# teensy_protocol_xl8r_3_6.net
KiCad netlist of a schematic drawn in EAGLE
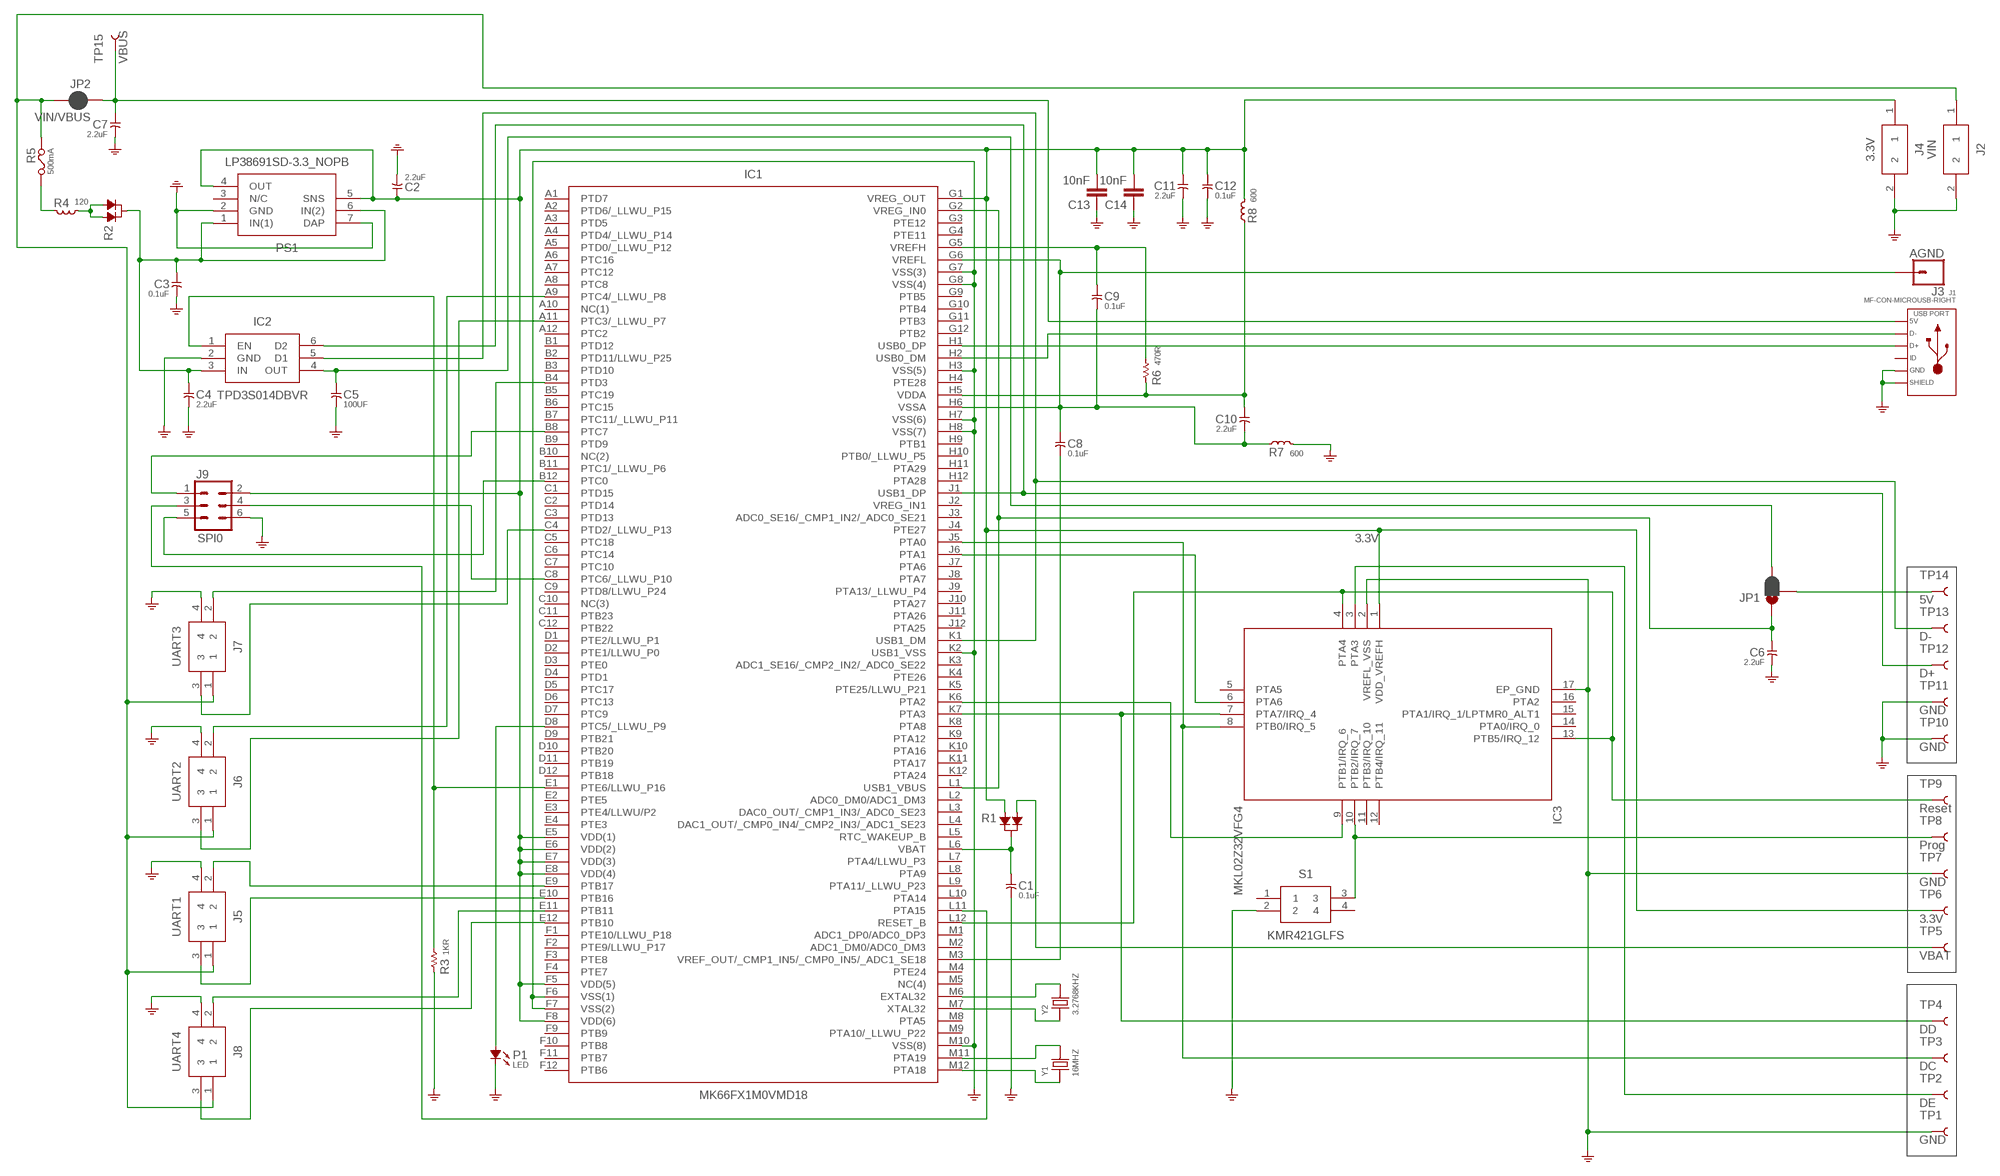
[diagram p0: schematic, sheet 1]

(export (version "E")
  (design (tool "Eeschema 10.0.6"))
  (components
    (comp (ref "C1")
      (value "0.1uF")
      (footprint "eagle-import:C0603")
      (fields (field (name "MF") "Murata Electronics") (field (name "MPN") "GRM188R71C104KA01D"))
      (libsource (lib "eagle-import") (part "CAPACITOR-0.1UF"))
    )
    (comp (ref "C2")
      (value "2.2uF")
      (footprint "eagle-import:C0805")
      (fields (field (name "MF") "Taiyo Yuden") (field (name "MPN") "TMK212B7225KG-TR"))
      (libsource (lib "eagle-import") (part "CAPACITOR-2.2UF"))
    )
    (comp (ref "C3")
      (value "0.1uF")
      (footprint "eagle-import:C0603")
      (fields (field (name "MF") "Murata Electronics") (field (name "MPN") "GRM188R71C104KA01D"))
      (libsource (lib "eagle-import") (part "CAPACITOR-0.1UF"))
    )
    (comp (ref "C4")
      (value "2.2uF")
      (footprint "eagle-import:C0805")
      (fields (field (name "MF") "Taiyo Yuden") (field (name "MPN") "TMK212B7225KG-TR"))
      (libsource (lib "eagle-import") (part "CAPACITOR-2.2UF"))
    )
    (comp (ref "C5")
      (value "100UF")
      (footprint "eagle-import:C1206")
      (libsource (lib "eagle-import") (part "CAPACITOR-100UF"))
    )
    (comp (ref "C6")
      (value "2.2uF")
      (footprint "eagle-import:C0805")
      (fields (field (name "MF") "Taiyo Yuden") (field (name "MPN") "TMK212B7225KG-TR"))
      (libsource (lib "eagle-import") (part "CAPACITOR-2.2UF"))
    )
    (comp (ref "C7")
      (value "2.2uF")
      (footprint "eagle-import:C0805")
      (fields (field (name "MF") "Taiyo Yuden") (field (name "MPN") "TMK212B7225KG-TR"))
      (libsource (lib "eagle-import") (part "CAPACITOR-2.2UF"))
    )
    (comp (ref "C8")
      (value "0.1uF")
      (footprint "eagle-import:C0603")
      (fields (field (name "MF") "Murata Electronics") (field (name "MPN") "GRM188R71C104KA01D"))
      (libsource (lib "eagle-import") (part "CAPACITOR-0.1UF"))
    )
    (comp (ref "C9")
      (value "0.1uF")
      (footprint "eagle-import:C0603")
      (fields (field (name "MF") "Murata Electronics") (field (name "MPN") "GRM188R71C104KA01D"))
      (libsource (lib "eagle-import") (part "CAPACITOR-0.1UF"))
    )
    (comp (ref "C10")
      (value "2.2uF")
      (footprint "eagle-import:C0805")
      (fields (field (name "MF") "Taiyo Yuden") (field (name "MPN") "TMK212B7225KG-TR"))
      (libsource (lib "eagle-import") (part "CAPACITOR-2.2UF"))
    )
    (comp (ref "C11")
      (value "2.2uF")
      (footprint "eagle-import:C0805")
      (fields (field (name "MF") "Taiyo Yuden") (field (name "MPN") "TMK212B7225KG-TR"))
      (libsource (lib "eagle-import") (part "CAPACITOR-2.2UF"))
    )
    (comp (ref "C12")
      (value "0.1uF")
      (footprint "eagle-import:C0603")
      (fields (field (name "MF") "Murata Electronics") (field (name "MPN") "GRM188R71C104KA01D"))
      (libsource (lib "eagle-import") (part "CAPACITOR-0.1UF"))
    )
    (comp (ref "C13")
      (value "10nF")
      (footprint "eagle-import:0603")
      (libsource (lib "eagle-import") (part "10NF-0603-50V-10%"))
    )
    (comp (ref "C14")
      (value "10nF")
      (footprint "eagle-import:0603")
      (libsource (lib "eagle-import") (part "10NF-0603-50V-10%"))
    )
    (comp (ref "IC1")
      (value "MK66FX1M0VMD18")
      (footprint "eagle-import:BGA144C100P12X12_1300X1300X170")
      (libsource (lib "eagle-import") (part "MK66FX1M0VMD18"))
    )
    (comp (ref "IC2")
      (value "TPD3S014DBVR")
      (footprint "eagle-import:SOT95P280X145-6N")
      (fields (field (name "RS_PART_NUMBER") "9009703P"))
      (libsource (lib "eagle-import") (part "TPD3S014DBVR"))
    )
    (comp (ref "IC3")
      (value "MKL02Z32VFG4")
      (footprint "eagle-import:QFN50P300X300X65-17N")
      (fields (field (name "RS_PART_NUMBER") "7884723"))
      (libsource (lib "eagle-import") (part "MKL02Z32VFG4"))
    )
    (comp (ref "J1")
      (value "MF-CON-MICROUSB-RIGHT")
      (footprint "eagle-import:MICROUSB-RIGHT")
      (fields (field (name "HOUSEPART") "YES"))
      (libsource (lib "eagle-import") (part "USB_MICRO_RIGHT"))
    )
    (comp (ref "J2")
      (value "VIN")
      (footprint "eagle-import:SM02B-GHS-TB")
      (fields
        (field (name "MANUFACTURER_PART_NUMBER") "SM02B-GHS-TB(LF)(SN)")
        (field (name "RS_PART_NUMBER") "7521790P")
      )
      (libsource (lib "eagle-import") (part "SM02B-GHS-TB(LF)(SN)"))
    )
    (comp (ref "J3")
      (value "AGND")
      (footprint "eagle-import:1X01")
      (libsource (lib "eagle-import") (part "CONN_01"))
    )
    (comp (ref "J4")
      (value "3.3V")
      (footprint "eagle-import:SM02B-GHS-TB")
      (fields
        (field (name "MANUFACTURER_PART_NUMBER") "SM02B-GHS-TB(LF)(SN)")
        (field (name "RS_PART_NUMBER") "7521790P")
      )
      (libsource (lib "eagle-import") (part "SM02B-GHS-TB(LF)(SN)"))
    )
    (comp (ref "J5")
      (value "UART1")
      (footprint "eagle-import:SM04B-GHS-TB")
      (fields
        (field (name "MANUFACTURER_PART_NUMBER") "SM04B-GHS-TB(LF)(SN)")
        (field (name "RS_PART_NUMBER") "7521797")
      )
      (libsource (lib "eagle-import") (part "SM04B-GHS-TB(LF)(SN)"))
    )
    (comp (ref "J6")
      (value "UART2")
      (footprint "eagle-import:SM04B-GHS-TB")
      (fields
        (field (name "MANUFACTURER_PART_NUMBER") "SM04B-GHS-TB(LF)(SN)")
        (field (name "RS_PART_NUMBER") "7521797")
      )
      (libsource (lib "eagle-import") (part "SM04B-GHS-TB(LF)(SN)"))
    )
    (comp (ref "J7")
      (value "UART3")
      (footprint "eagle-import:SM04B-GHS-TB")
      (fields
        (field (name "MANUFACTURER_PART_NUMBER") "SM04B-GHS-TB(LF)(SN)")
        (field (name "RS_PART_NUMBER") "7521797")
      )
      (libsource (lib "eagle-import") (part "SM04B-GHS-TB(LF)(SN)"))
    )
    (comp (ref "J8")
      (value "UART4")
      (footprint "eagle-import:SM04B-GHS-TB")
      (fields
        (field (name "MANUFACTURER_PART_NUMBER") "SM04B-GHS-TB(LF)(SN)")
        (field (name "RS_PART_NUMBER") "7521797")
      )
      (libsource (lib "eagle-import") (part "SM04B-GHS-TB(LF)(SN)"))
    )
    (comp (ref "J9")
      (value "SPI0")
      (footprint "eagle-import:2X3")
      (libsource (lib "eagle-import") (part "CONN_03X2FEMALE"))
    )
    (comp (ref "JP1")
      (value "JUMPER-SMT_3_1-NC_PASTE_SILK")
      (footprint "eagle-import:SMT-JUMPER_3_1-NC_PASTE_SILK")
      (libsource (lib "eagle-import") (part "JUMPER-SMT_3_1-NC_PASTE_SILK"))
    )
    (comp (ref "JP2")
      (value "VIN/VBUS")
      (footprint "eagle-import:SMT-JUMPER_2_NC_PASTE_SILK")
      (libsource (lib "eagle-import") (part "JUMPER-SMT_2_NC_PASTE_SILK"))
    )
    (comp (ref "P1")
      (value "LED")
      (footprint "eagle-import:LED-0805")
      (fields (field (name "MF") "ROHM Semiconductor") (field (name "MPN") "SML-211DTT86"))
      (libsource (lib "eagle-import") (part "LED"))
    )
    (comp (ref "PS1")
      (value "LP38691SD-3.3_NOPB")
      (footprint "eagle-import:SON95P300X300X80-7N")
      (fields
        (field (name "MANUFACTURER_PART_NUMBER") "LP38691SD-3.3/NOPB")
        (field (name "RS_PART_NUMBER") "7616605P")
      )
      (libsource (lib "eagle-import") (part "LP38691SD-3.3_NOPB"))
    )
    (comp (ref "R1")
      (value "DIODE_DUAL")
      (footprint "eagle-import:SOT-23")
      (fields (field (name "MF") "NXP Semiconductors") (field (name "MPN") "BAT54C,215"))
      (libsource (lib "eagle-import") (part "DIODE_DUAL"))
    )
    (comp (ref "R2")
      (value "DIODE_DUAL")
      (footprint "eagle-import:SOT-23")
      (fields (field (name "MF") "NXP Semiconductors") (field (name "MPN") "BAT54C,215"))
      (libsource (lib "eagle-import") (part "DIODE_DUAL"))
    )
    (comp (ref "R3")
      (value "1KR")
      (footprint "eagle-import:R0603")
      (fields (field (name "MF") "Vishay") (field (name "MPN") "CRCW06031K00FKEA"))
      (libsource (lib "eagle-import") (part "RESISTOR-1KR"))
    )
    (comp (ref "R4")
      (value "120")
      (footprint "eagle-import:L0603")
      (fields (field (name "MF") "Murata Electronics") (field (name "MPN") " BLM18AG601SN1D"))
      (libsource (lib "eagle-import") (part "FERRITE"))
    )
    (comp (ref "R5")
      (value "500mA")
      (footprint "eagle-import:F0805")
      (fields (field (name "MF") "Bel Fuse") (field (name "MPN") "0ZCK0050FF2E"))
      (libsource (lib "eagle-import") (part "FUSE"))
    )
    (comp (ref "R6")
      (value "470R")
      (footprint "eagle-import:R0603")
      (fields (field (name "MF") "Vishay") (field (name "MPN") "CRCW0603470RFKEA"))
      (libsource (lib "eagle-import") (part "RESISTOR-470R"))
    )
    (comp (ref "R7")
      (value "600")
      (footprint "eagle-import:L0603")
      (fields (field (name "MF") "Murata Electronics") (field (name "MPN") " BLM18AG601SN1D"))
      (libsource (lib "eagle-import") (part "FERRITE"))
    )
    (comp (ref "R8")
      (value "600")
      (footprint "eagle-import:L0603")
      (fields (field (name "MF") "Murata Electronics") (field (name "MPN") " BLM18AG601SN1D"))
      (libsource (lib "eagle-import") (part "FERRITE"))
    )
    (comp (ref "S1")
      (value "KMR421GLFS")
      (footprint "eagle-import:KMR_2")
      (libsource (lib "eagle-import") (part "KMR421GLFS"))
    )
    (comp (ref "TP1")
      (value "GND")
      (footprint "eagle-import:PAD.03X.03")
      (libsource (lib "eagle-import") (part "TEST-POINT3"))
    )
    (comp (ref "TP2")
      (value "DE")
      (footprint "eagle-import:PAD.03X.03")
      (libsource (lib "eagle-import") (part "TEST-POINT3"))
    )
    (comp (ref "TP3")
      (value "DC")
      (footprint "eagle-import:PAD.03X.03")
      (libsource (lib "eagle-import") (part "TEST-POINT3"))
    )
    (comp (ref "TP4")
      (value "DD")
      (footprint "eagle-import:PAD.03X.03")
      (libsource (lib "eagle-import") (part "TEST-POINT3"))
    )
    (comp (ref "TP5")
      (value "VBAT")
      (footprint "eagle-import:PAD.03X.03")
      (libsource (lib "eagle-import") (part "TEST-POINT3"))
    )
    (comp (ref "TP6")
      (value "3.3V")
      (footprint "eagle-import:PAD.03X.03")
      (libsource (lib "eagle-import") (part "TEST-POINT3"))
    )
    (comp (ref "TP7")
      (value "GND")
      (footprint "eagle-import:PAD.03X.03")
      (libsource (lib "eagle-import") (part "TEST-POINT3"))
    )
    (comp (ref "TP8")
      (value "Prog")
      (footprint "eagle-import:PAD.03X.03")
      (libsource (lib "eagle-import") (part "TEST-POINT3"))
    )
    (comp (ref "TP9")
      (value "Reset")
      (footprint "eagle-import:PAD.03X.03")
      (libsource (lib "eagle-import") (part "TEST-POINT3"))
    )
    (comp (ref "TP10")
      (value "GND")
      (footprint "eagle-import:PAD.03X.03")
      (libsource (lib "eagle-import") (part "TEST-POINT3"))
    )
    (comp (ref "TP11")
      (value "GND")
      (footprint "eagle-import:PAD.03X.03")
      (libsource (lib "eagle-import") (part "TEST-POINT3"))
    )
    (comp (ref "TP12")
      (value "D+")
      (footprint "eagle-import:PAD.03X.03")
      (libsource (lib "eagle-import") (part "TEST-POINT3"))
    )
    (comp (ref "TP13")
      (value "D-")
      (footprint "eagle-import:PAD.03X.03")
      (libsource (lib "eagle-import") (part "TEST-POINT3"))
    )
    (comp (ref "TP14")
      (value "5V")
      (footprint "eagle-import:PAD.03X.03")
      (libsource (lib "eagle-import") (part "TEST-POINT3"))
    )
    (comp (ref "TP15")
      (value "VBUS")
      (footprint "eagle-import:PAD.03X.03")
      (libsource (lib "eagle-import") (part "TEST-POINT3"))
    )
    (comp (ref "Y1")
      (value "16MHZ")
      (footprint "eagle-import:X2-SMD-5.0X3.2X1.3MM")
      (fields (field (name "MPN") "X053201602002"))
      (libsource (lib "eagle-import") (part "SMD-CRYSTAL-16MHZ-8PF-20PPM-40R(2P-5.0X3.2MM)"))
    )
    (comp (ref "Y2")
      (value "3.2768KHZ")
      (footprint "eagle-import:X2-SMD-L2.0X1.2X0.55MM")
      (fields (field (name "MPN") "FC-12M"))
      (libsource (lib "eagle-import") (part "SMD-CRYSTAL-32.768KHZ-12.5PF-20PPM-90K(2P-L2.0X1.2MM)"))
    )
  )
  (nets
    (net (code "1") (name "/3.3V") (class "Default")
      (node (ref "C11") (pin "1") (pinfunction "1_1") (pintype "passive"))
      (node (ref "C12") (pin "1") (pinfunction "1_1") (pintype "passive"))
      (node (ref "C13") (pin "2") (pinfunction "2_2") (pintype "passive"))
      (node (ref "C14") (pin "2") (pinfunction "2_2") (pintype "passive"))
      (node (ref "C2") (pin "1") (pinfunction "1_1") (pintype "passive"))
      (node (ref "IC1") (pin "E5") (pinfunction "VDD(1)_E5") (pintype "passive"))
      (node (ref "IC1") (pin "E6") (pinfunction "VDD(2)_E6") (pintype "passive"))
      (node (ref "IC1") (pin "E7") (pinfunction "VDD(3)_E7") (pintype "passive"))
      (node (ref "IC1") (pin "E8") (pinfunction "VDD(4)_E8") (pintype "passive"))
      (node (ref "IC1") (pin "F5") (pinfunction "VDD(5)_F5") (pintype "passive"))
      (node (ref "IC1") (pin "F8") (pinfunction "VDD(6)_F8") (pintype "passive"))
      (node (ref "IC1") (pin "G1") (pinfunction "VREG_OUT_G1") (pintype "passive"))
      (node (ref "IC3") (pin "1") (pinfunction "VDD_VREFH_1") (pintype "power_in"))
      (node (ref "J4") (pin "1") (pinfunction "1_1") (pintype "passive"))
      (node (ref "J9") (pin "2") (pinfunction "2_2") (pintype "bidirectional"))
      (node (ref "PS1") (pin "4") (pinfunction "OUT_4") (pintype "output"))
      (node (ref "PS1") (pin "5") (pinfunction "SNS_5") (pintype "output"))
      (node (ref "R1") (pin "2") (pinfunction "2_2") (pintype "bidirectional"))
      (node (ref "R8") (pin "2") (pinfunction "2_2") (pintype "passive"))
      (node (ref "TP6") (pin "P$1") (pinfunction "1_P$1") (pintype "bidirectional"))
    )
    (net (code "2") (name "GND") (class "Default")
      (node (ref "C1") (pin "2") (pinfunction "2_2") (pintype "passive"))
      (node (ref "C11") (pin "2") (pinfunction "2_2") (pintype "passive"))
      (node (ref "C12") (pin "2") (pinfunction "2_2") (pintype "passive"))
      (node (ref "C13") (pin "1") (pinfunction "1_1") (pintype "passive"))
      (node (ref "C14") (pin "1") (pinfunction "1_1") (pintype "passive"))
      (node (ref "C2") (pin "2") (pinfunction "2_2") (pintype "passive"))
      (node (ref "C3") (pin "2") (pinfunction "2_2") (pintype "passive"))
      (node (ref "C4") (pin "2") (pinfunction "2_2") (pintype "passive"))
      (node (ref "C5") (pin "2") (pinfunction "2_2") (pintype "passive"))
      (node (ref "C6") (pin "2") (pinfunction "2_2") (pintype "passive"))
      (node (ref "C7") (pin "2") (pinfunction "2_2") (pintype "passive"))
      (node (ref "IC1") (pin "F6") (pinfunction "VSS(1)_F6") (pintype "passive"))
      (node (ref "IC1") (pin "F7") (pinfunction "VSS(2)_F7") (pintype "passive"))
      (node (ref "IC1") (pin "G7") (pinfunction "VSS(3)_G7") (pintype "passive"))
      (node (ref "IC1") (pin "G8") (pinfunction "VSS(4)_G8") (pintype "passive"))
      (node (ref "IC1") (pin "H3") (pinfunction "VSS(5)_H3") (pintype "passive"))
      (node (ref "IC1") (pin "H7") (pinfunction "VSS(6)_H7") (pintype "passive"))
      (node (ref "IC1") (pin "H8") (pinfunction "VSS(7)_H8") (pintype "passive"))
      (node (ref "IC1") (pin "K2") (pinfunction "USB1_VSS_K2") (pintype "passive"))
      (node (ref "IC1") (pin "M10") (pinfunction "VSS(8)_M10") (pintype "passive"))
      (node (ref "IC2") (pin "2") (pinfunction "GND_2") (pintype "power_in"))
      (node (ref "IC3") (pin "17") (pinfunction "EP_GND_17") (pintype "power_in"))
      (node (ref "IC3") (pin "2") (pinfunction "VREFL_VSS_2") (pintype "power_in"))
      (node (ref "J1") (pin "5") (pinfunction "GND_5") (pintype "power_in"))
      (node (ref "J1") (pin "S1") (pinfunction "SLD_S1") (pintype "power_in"))
      (node (ref "J1") (pin "S2") (pinfunction "SLD_S2") (pintype "power_in"))
      (node (ref "J1") (pin "S3") (pinfunction "SLD_S3") (pintype "power_in"))
      (node (ref "J1") (pin "S4") (pinfunction "SLD_S4") (pintype "power_in"))
      (node (ref "J1") (pin "S5") (pinfunction "SLD_S5") (pintype "power_in"))
      (node (ref "J1") (pin "S6") (pinfunction "SLD_S6") (pintype "power_in"))
      (node (ref "J2") (pin "2") (pinfunction "2_2") (pintype "passive"))
      (node (ref "J4") (pin "2") (pinfunction "2_2") (pintype "passive"))
      (node (ref "J5") (pin "4") (pinfunction "4_4") (pintype "passive"))
      (node (ref "J6") (pin "4") (pinfunction "4_4") (pintype "passive"))
      (node (ref "J7") (pin "4") (pinfunction "4_4") (pintype "passive"))
      (node (ref "J8") (pin "4") (pinfunction "4_4") (pintype "passive"))
      (node (ref "J9") (pin "6") (pinfunction "6_6") (pintype "bidirectional"))
      (node (ref "P1") (pin "-") (pinfunction "-_-") (pintype "passive"))
      (node (ref "PS1") (pin "2") (pinfunction "GND_2") (pintype "power_in"))
      (node (ref "PS1") (pin "7") (pinfunction "DAP_7") (pintype "passive"))
      (node (ref "R3") (pin "1") (pinfunction "1_1") (pintype "passive"))
      (node (ref "R7") (pin "2") (pinfunction "2_2") (pintype "passive"))
      (node (ref "S1") (pin "2") (pinfunction "2_2") (pintype "passive"))
      (node (ref "TP1") (pin "P$1") (pinfunction "1_P$1") (pintype "bidirectional"))
      (node (ref "TP10") (pin "P$1") (pinfunction "1_P$1") (pintype "bidirectional"))
      (node (ref "TP11") (pin "P$1") (pinfunction "1_P$1") (pintype "bidirectional"))
      (node (ref "TP7") (pin "P$1") (pinfunction "1_P$1") (pintype "bidirectional"))
    )
    (net (code "3") (name "Net-(IC1-EXTAL32)") (class "Default")
      (node (ref "IC1") (pin "M6") (pinfunction "EXTAL32_M6") (pintype "passive"))
      (node (ref "Y2") (pin "2") (pinfunction "2_2") (pintype "passive"))
    )
    (net (code "4") (name "Net-(IC1-PTA0)") (class "Default")
      (node (ref "IC1") (pin "J5") (pinfunction "PTA0_J5") (pintype "passive"))
      (node (ref "IC3") (pin "8") (pinfunction "PTB0/IRQ_5_8") (pintype "passive"))
      (node (ref "TP3") (pin "P$1") (pinfunction "1_P$1") (pintype "bidirectional"))
    )
    (net (code "5") (name "Net-(IC1-PTA1)") (class "Default")
      (node (ref "IC1") (pin "J6") (pinfunction "PTA1_J6") (pintype "passive"))
      (node (ref "IC3") (pin "6") (pinfunction "PTA6_6") (pintype "passive"))
    )
    (net (code "6") (name "Net-(IC1-PTA2)") (class "Default")
      (node (ref "IC1") (pin "K6") (pinfunction "PTA2_K6") (pintype "passive"))
      (node (ref "IC3") (pin "9") (pinfunction "PTB1/IRQ_6_9") (pintype "passive"))
    )
    (net (code "7") (name "Net-(IC1-PTA3)") (class "Default")
      (node (ref "IC1") (pin "K7") (pinfunction "PTA3_K7") (pintype "passive"))
      (node (ref "IC3") (pin "7") (pinfunction "PTA7/IRQ_4_7") (pintype "passive"))
      (node (ref "TP4") (pin "P$1") (pinfunction "1_P$1") (pintype "bidirectional"))
    )
    (net (code "8") (name "Net-(IC1-PTA15)") (class "Default")
      (node (ref "IC1") (pin "L11") (pinfunction "PTA15_L11") (pintype "passive"))
      (node (ref "J9") (pin "3") (pinfunction "3_3") (pintype "bidirectional"))
    )
    (net (code "9") (name "Net-(IC1-PTA18)") (class "Default")
      (node (ref "IC1") (pin "M12") (pinfunction "PTA18_M12") (pintype "passive"))
      (node (ref "Y1") (pin "1") (pinfunction "1_1") (pintype "passive"))
    )
    (net (code "10") (name "Net-(IC1-PTA19)") (class "Default")
      (node (ref "IC1") (pin "M11") (pinfunction "PTA19_M11") (pintype "passive"))
      (node (ref "Y1") (pin "2") (pinfunction "2_2") (pintype "passive"))
    )
    (net (code "11") (name "Net-(IC1-PTB10)") (class "Default")
      (node (ref "IC1") (pin "E12") (pinfunction "PTB10_E12") (pintype "passive"))
      (node (ref "J8") (pin "3") (pinfunction "3_3") (pintype "passive"))
    )
    (net (code "12") (name "Net-(IC1-PTB11)") (class "Default")
      (node (ref "IC1") (pin "E11") (pinfunction "PTB11_E11") (pintype "passive"))
      (node (ref "J8") (pin "2") (pinfunction "2_2") (pintype "passive"))
    )
    (net (code "13") (name "Net-(IC1-PTB16)") (class "Default")
      (node (ref "IC1") (pin "E10") (pinfunction "PTB16_E10") (pintype "passive"))
      (node (ref "J5") (pin "3") (pinfunction "3_3") (pintype "passive"))
    )
    (net (code "14") (name "Net-(IC1-PTB17)") (class "Default")
      (node (ref "IC1") (pin "E9") (pinfunction "PTB17_E9") (pintype "passive"))
      (node (ref "J5") (pin "2") (pinfunction "2_2") (pintype "passive"))
    )
    (net (code "15") (name "Net-(IC1-PTC0)") (class "Default")
      (node (ref "IC1") (pin "B12") (pinfunction "PTC0_B12") (pintype "passive"))
      (node (ref "J9") (pin "5") (pinfunction "5_5") (pintype "bidirectional"))
    )
    (net (code "16") (name "Net-(IC1-PTC3{slash}_LLWU_P7)") (class "Default")
      (node (ref "IC1") (pin "A11") (pinfunction "PTC3/_LLWU_P7_A11") (pintype "passive"))
      (node (ref "J6") (pin "3") (pinfunction "3_3") (pintype "passive"))
    )
    (net (code "17") (name "Net-(IC1-PTC4{slash}_LLWU_P8)") (class "Default")
      (node (ref "IC1") (pin "A9") (pinfunction "PTC4/_LLWU_P8_A9") (pintype "passive"))
      (node (ref "J6") (pin "2") (pinfunction "2_2") (pintype "passive"))
    )
    (net (code "18") (name "Net-(IC1-PTC5{slash}_LLWU_P9)") (class "Default")
      (node (ref "IC1") (pin "D8") (pinfunction "PTC5/_LLWU_P9_D8") (pintype "passive"))
      (node (ref "P1") (pin "+") (pinfunction "+_+") (pintype "passive"))
    )
    (net (code "19") (name "Net-(IC1-PTC6{slash}_LLWU_P10)") (class "Default")
      (node (ref "IC1") (pin "C8") (pinfunction "PTC6/_LLWU_P10_C8") (pintype "passive"))
      (node (ref "J9") (pin "4") (pinfunction "4_4") (pintype "bidirectional"))
    )
    (net (code "20") (name "Net-(IC1-PTC7)") (class "Default")
      (node (ref "IC1") (pin "B8") (pinfunction "PTC7_B8") (pintype "passive"))
      (node (ref "J9") (pin "1") (pinfunction "1_1") (pintype "bidirectional"))
    )
    (net (code "21") (name "Net-(IC1-PTD2{slash}_LLWU_P13)") (class "Default")
      (node (ref "IC1") (pin "C4") (pinfunction "PTD2/_LLWU_P13_C4") (pintype "passive"))
      (node (ref "J7") (pin "3") (pinfunction "3_3") (pintype "passive"))
    )
    (net (code "22") (name "Net-(IC1-PTD3)") (class "Default")
      (node (ref "IC1") (pin "B4") (pinfunction "PTD3_B4") (pintype "passive"))
      (node (ref "J7") (pin "2") (pinfunction "2_2") (pintype "passive"))
    )
    (net (code "23") (name "Net-(IC1-PTE6{slash}LLWU_P16)") (class "Default")
      (node (ref "IC1") (pin "E1") (pinfunction "PTE6/LLWU_P16_E1") (pintype "passive"))
      (node (ref "IC2") (pin "1") (pinfunction "EN_1") (pintype "input"))
      (node (ref "R3") (pin "2") (pinfunction "2_2") (pintype "passive"))
    )
    (net (code "24") (name "Net-(IC1-RESET_B)") (class "Default")
      (node (ref "IC1") (pin "L12") (pinfunction "RESET_B_L12") (pintype "passive"))
      (node (ref "IC3") (pin "13") (pinfunction "PTB5/IRQ_12_13") (pintype "passive"))
      (node (ref "IC3") (pin "4") (pinfunction "PTA4_4") (pintype "passive"))
      (node (ref "TP9") (pin "P$1") (pinfunction "1_P$1") (pintype "bidirectional"))
    )
    (net (code "25") (name "Net-(IC1-USB0_DM)") (class "Default")
      (node (ref "IC1") (pin "H2") (pinfunction "USB0_DM_H2") (pintype "passive"))
      (node (ref "J1") (pin "2") (pinfunction "D-_2") (pintype "bidirectional"))
    )
    (net (code "26") (name "Net-(IC1-USB0_DP)") (class "Default")
      (node (ref "IC1") (pin "H1") (pinfunction "USB0_DP_H1") (pintype "passive"))
      (node (ref "J1") (pin "3") (pinfunction "D+_3") (pintype "bidirectional"))
    )
    (net (code "27") (name "Net-(IC1-USB1_DM)") (class "Default")
      (node (ref "IC1") (pin "K1") (pinfunction "USB1_DM_K1") (pintype "passive"))
      (node (ref "IC2") (pin "5") (pinfunction "D1_5") (pintype "bidirectional"))
      (node (ref "TP13") (pin "P$1") (pinfunction "1_P$1") (pintype "bidirectional"))
    )
    (net (code "28") (name "Net-(IC1-USB1_DP)") (class "Default")
      (node (ref "IC1") (pin "J1") (pinfunction "USB1_DP_J1") (pintype "passive"))
      (node (ref "IC2") (pin "6") (pinfunction "D2_6") (pintype "bidirectional"))
      (node (ref "TP12") (pin "P$1") (pinfunction "1_P$1") (pintype "bidirectional"))
    )
    (net (code "29") (name "Net-(IC1-USB1_VBUS)") (class "Default")
      (node (ref "C6") (pin "1") (pinfunction "1_1") (pintype "passive"))
      (node (ref "IC1") (pin "G2") (pinfunction "VREG_IN0_G2") (pintype "passive"))
      (node (ref "IC1") (pin "L1") (pinfunction "USB1_VBUS_L1") (pintype "passive"))
      (node (ref "JP1") (pin "1") (pinfunction "1_1") (pintype "passive"))
    )
    (net (code "30") (name "Net-(IC1-VBAT)") (class "Default")
      (node (ref "C1") (pin "1") (pinfunction "1_1") (pintype "passive"))
      (node (ref "IC1") (pin "L6") (pinfunction "VBAT_L6") (pintype "passive"))
      (node (ref "R1") (pin "3") (pinfunction "3_3") (pintype "bidirectional"))
    )
    (net (code "31") (name "Net-(IC1-VDDA)") (class "Default")
      (node (ref "C10") (pin "1") (pinfunction "1_1") (pintype "passive"))
      (node (ref "IC1") (pin "H5") (pinfunction "VDDA_H5") (pintype "passive"))
      (node (ref "R6") (pin "1") (pinfunction "1_1") (pintype "passive"))
      (node (ref "R8") (pin "1") (pinfunction "1_1") (pintype "passive"))
    )
    (net (code "32") (name "Net-(IC1-VREFH)") (class "Default")
      (node (ref "C9") (pin "1") (pinfunction "1_1") (pintype "passive"))
      (node (ref "IC1") (pin "G5") (pinfunction "VREFH_G5") (pintype "passive"))
      (node (ref "R6") (pin "2") (pinfunction "2_2") (pintype "passive"))
    )
    (net (code "33") (name "Net-(IC1-VREFL)") (class "Default")
      (node (ref "C10") (pin "2") (pinfunction "2_2") (pintype "passive"))
      (node (ref "C8") (pin "1") (pinfunction "1_1") (pintype "passive"))
      (node (ref "C9") (pin "2") (pinfunction "2_2") (pintype "passive"))
      (node (ref "IC1") (pin "G6") (pinfunction "VREFL_G6") (pintype "passive"))
      (node (ref "IC1") (pin "H6") (pinfunction "VSSA_H6") (pintype "passive"))
      (node (ref "J3") (pin "1") (pinfunction "1_1") (pintype "passive"))
      (node (ref "R7") (pin "1") (pinfunction "1_1") (pintype "passive"))
    )
    (net (code "34") (name "Net-(IC1-VREF_OUT{slash}_CMP1_IN5{slash}_CMP0_IN5{slash}_ADC1_SE18)") (class "Default")
      (node (ref "C8") (pin "2") (pinfunction "2_2") (pintype "passive"))
      (node (ref "IC1") (pin "M3") (pinfunction "VREF_OUT/_CMP1_IN5/_CMP0_IN5/_ADC1_SE18_M3") (pintype "passive"))
    )
    (net (code "35") (name "Net-(IC1-XTAL32)") (class "Default")
      (node (ref "IC1") (pin "M7") (pinfunction "XTAL32_M7") (pintype "passive"))
      (node (ref "Y2") (pin "1") (pinfunction "1_1") (pintype "passive"))
    )
    (net (code "36") (name "Net-(IC2-IN)") (class "Default")
      (node (ref "C3") (pin "1") (pinfunction "1_1") (pintype "passive"))
      (node (ref "C4") (pin "1") (pinfunction "1_1") (pintype "passive"))
      (node (ref "IC2") (pin "3") (pinfunction "IN_3") (pintype "input"))
      (node (ref "PS1") (pin "1") (pinfunction "IN(1)_1") (pintype "input"))
      (node (ref "PS1") (pin "6") (pinfunction "IN(2)_6") (pintype "input"))
      (node (ref "R2") (pin "3") (pinfunction "3_3") (pintype "bidirectional"))
    )
    (net (code "37") (name "Net-(IC2-OUT)") (class "Default")
      (node (ref "C5") (pin "1") (pinfunction "1_1") (pintype "passive"))
      (node (ref "IC2") (pin "4") (pinfunction "OUT_4") (pintype "output"))
      (node (ref "JP1") (pin "3") (pinfunction "3_3") (pintype "passive"))
    )
    (net (code "38") (name "Net-(IC3-PTA3)") (class "Default")
      (node (ref "IC3") (pin "3") (pinfunction "PTA3_3") (pintype "passive"))
      (node (ref "TP2") (pin "P$1") (pinfunction "1_P$1") (pintype "bidirectional"))
    )
    (net (code "39") (name "Net-(IC3-PTB2{slash}IRQ_7)") (class "Default")
      (node (ref "IC3") (pin "10") (pinfunction "PTB2/IRQ_7_10") (pintype "passive"))
      (node (ref "S1") (pin "3") (pinfunction "3_3") (pintype "passive"))
      (node (ref "TP8") (pin "P$1") (pinfunction "1_P$1") (pintype "bidirectional"))
    )
    (net (code "40") (name "Net-(J1-5V)") (class "Default")
      (node (ref "C7") (pin "1") (pinfunction "1_1") (pintype "passive"))
      (node (ref "J1") (pin "1") (pinfunction "5V_1") (pintype "power_in"))
      (node (ref "JP2") (pin "1") (pinfunction "1_1") (pintype "passive"))
      (node (ref "TP15") (pin "P$1") (pinfunction "1_P$1") (pintype "bidirectional"))
    )
    (net (code "41") (name "Net-(J2-Pad1)") (class "Default")
      (node (ref "J2") (pin "1") (pinfunction "1_1") (pintype "passive"))
      (node (ref "J5") (pin "1") (pinfunction "1_1") (pintype "passive"))
      (node (ref "J6") (pin "1") (pinfunction "1_1") (pintype "passive"))
      (node (ref "J7") (pin "1") (pinfunction "1_1") (pintype "passive"))
      (node (ref "J8") (pin "1") (pinfunction "1_1") (pintype "passive"))
      (node (ref "JP2") (pin "2") (pinfunction "2_2") (pintype "passive"))
      (node (ref "R5") (pin "1") (pinfunction "1_1") (pintype "bidirectional"))
    )
    (net (code "42") (name "Net-(R2-Pad1)") (class "Default")
      (node (ref "R2") (pin "1") (pinfunction "1_1") (pintype "bidirectional"))
      (node (ref "R2") (pin "2") (pinfunction "2_2") (pintype "bidirectional"))
      (node (ref "R4") (pin "2") (pinfunction "2_2") (pintype "passive"))
    )
    (net (code "43") (name "Net-(R4-Pad1)") (class "Default")
      (node (ref "R4") (pin "1") (pinfunction "1_1") (pintype "passive"))
      (node (ref "R5") (pin "2") (pinfunction "2_2") (pintype "bidirectional"))
    )
    (net (code "44") (name "Net-(TP5-1)") (class "Default")
      (node (ref "R1") (pin "1") (pinfunction "1_1") (pintype "bidirectional"))
      (node (ref "TP5") (pin "P$1") (pinfunction "1_P$1") (pintype "bidirectional"))
    )
    (net (code "45") (name "Net-(TP14-1)") (class "Default")
      (node (ref "JP1") (pin "2") (pinfunction "2_2") (pintype "passive"))
      (node (ref "TP14") (pin "P$1") (pinfunction "1_P$1") (pintype "bidirectional"))
    )
    (net (code "46") (name "unconnected-(IC1-ADC0_DM0{slash}ADC1_DM3-PadL2)") (class "Default")
      (node (ref "IC1") (pin "L2") (pinfunction "ADC0_DM0/ADC1_DM3_L2") (pintype "passive"))
    )
    (net (code "47") (name "unconnected-(IC1-ADC0_SE16{slash}_CMP1_IN2{slash}_ADC0_SE21-PadJ3)") (class "Default")
      (node (ref "IC1") (pin "J3") (pinfunction "ADC0_SE16/_CMP1_IN2/_ADC0_SE21_J3") (pintype "passive"))
    )
    (net (code "48") (name "unconnected-(IC1-ADC1_DM0{slash}ADC0_DM3-PadM2)") (class "Default")
      (node (ref "IC1") (pin "M2") (pinfunction "ADC1_DM0/ADC0_DM3_M2") (pintype "passive"))
    )
    (net (code "49") (name "unconnected-(IC1-ADC1_DP0{slash}ADC0_DP3-PadM1)") (class "Default")
      (node (ref "IC1") (pin "M1") (pinfunction "ADC1_DP0/ADC0_DP3_M1") (pintype "passive"))
    )
    (net (code "50") (name "unconnected-(IC1-ADC1_SE16{slash}_CMP2_IN2{slash}_ADC0_SE22-PadK3)") (class "Default")
      (node (ref "IC1") (pin "K3") (pinfunction "ADC1_SE16/_CMP2_IN2/_ADC0_SE22_K3") (pintype "passive"))
    )
    (net (code "51") (name "unconnected-(IC1-DAC0_OUT{slash}_CMP1_IN3{slash}_ADC0_SE23-PadL3)") (class "Default")
      (node (ref "IC1") (pin "L3") (pinfunction "DAC0_OUT/_CMP1_IN3/_ADC0_SE23_L3") (pintype "passive"))
    )
    (net (code "52") (name "unconnected-(IC1-DAC1_OUT{slash}_CMP0_IN4{slash}_CMP2_IN3{slash}_ADC1_SE23-PadL4)") (class "Default")
      (node (ref "IC1") (pin "L4") (pinfunction "DAC1_OUT/_CMP0_IN4/_CMP2_IN3/_ADC1_SE23_L4") (pintype "passive"))
    )
    (net (code "53") (name "unconnected-(IC1-NC(1)-PadA10)") (class "Default")
      (node (ref "IC1") (pin "A10") (pinfunction "NC(1)_A10") (pintype "passive"))
    )
    (net (code "54") (name "unconnected-(IC1-NC(2)-PadB10)") (class "Default")
      (node (ref "IC1") (pin "B10") (pinfunction "NC(2)_B10") (pintype "passive"))
    )
    (net (code "55") (name "unconnected-(IC1-NC(3)-PadC10)") (class "Default")
      (node (ref "IC1") (pin "C10") (pinfunction "NC(3)_C10") (pintype "passive"))
    )
    (net (code "56") (name "unconnected-(IC1-NC(4)-PadM5)") (class "Default")
      (node (ref "IC1") (pin "M5") (pinfunction "NC(4)_M5") (pintype "passive"))
    )
    (net (code "57") (name "unconnected-(IC1-PTA4{slash}LLWU_P3-PadL7)") (class "Default")
      (node (ref "IC1") (pin "L7") (pinfunction "PTA4/LLWU_P3_L7") (pintype "passive"))
    )
    (net (code "58") (name "unconnected-(IC1-PTA5-PadM8)") (class "Default")
      (node (ref "IC1") (pin "M8") (pinfunction "PTA5_M8") (pintype "passive"))
    )
    (net (code "59") (name "unconnected-(IC1-PTA6-PadJ7)") (class "Default")
      (node (ref "IC1") (pin "J7") (pinfunction "PTA6_J7") (pintype "passive"))
    )
    (net (code "60") (name "unconnected-(IC1-PTA7-PadJ8)") (class "Default")
      (node (ref "IC1") (pin "J8") (pinfunction "PTA7_J8") (pintype "passive"))
    )
    (net (code "61") (name "unconnected-(IC1-PTA8-PadK8)") (class "Default")
      (node (ref "IC1") (pin "K8") (pinfunction "PTA8_K8") (pintype "passive"))
    )
    (net (code "62") (name "unconnected-(IC1-PTA9-PadL8)") (class "Default")
      (node (ref "IC1") (pin "L8") (pinfunction "PTA9_L8") (pintype "passive"))
    )
    (net (code "63") (name "unconnected-(IC1-PTA10{slash}_LLWU_P22-PadM9)") (class "Default")
      (node (ref "IC1") (pin "M9") (pinfunction "PTA10/_LLWU_P22_M9") (pintype "passive"))
    )
    (net (code "64") (name "unconnected-(IC1-PTA11{slash}_LLWU_P23-PadL9)") (class "Default")
      (node (ref "IC1") (pin "L9") (pinfunction "PTA11/_LLWU_P23_L9") (pintype "passive"))
    )
    (net (code "65") (name "unconnected-(IC1-PTA12-PadK9)") (class "Default")
      (node (ref "IC1") (pin "K9") (pinfunction "PTA12_K9") (pintype "passive"))
    )
    (net (code "66") (name "unconnected-(IC1-PTA13{slash}_LLWU_P4-PadJ9)") (class "Default")
      (node (ref "IC1") (pin "J9") (pinfunction "PTA13/_LLWU_P4_J9") (pintype "passive"))
    )
    (net (code "67") (name "unconnected-(IC1-PTA14-PadL10)") (class "Default")
      (node (ref "IC1") (pin "L10") (pinfunction "PTA14_L10") (pintype "passive"))
    )
    (net (code "68") (name "unconnected-(IC1-PTA16-PadK10)") (class "Default")
      (node (ref "IC1") (pin "K10") (pinfunction "PTA16_K10") (pintype "passive"))
    )
    (net (code "69") (name "unconnected-(IC1-PTA17-PadK11)") (class "Default")
      (node (ref "IC1") (pin "K11") (pinfunction "PTA17_K11") (pintype "passive"))
    )
    (net (code "70") (name "unconnected-(IC1-PTA24-PadK12)") (class "Default")
      (node (ref "IC1") (pin "K12") (pinfunction "PTA24_K12") (pintype "passive"))
    )
    (net (code "71") (name "unconnected-(IC1-PTA25-PadJ12)") (class "Default")
      (node (ref "IC1") (pin "J12") (pinfunction "PTA25_J12") (pintype "passive"))
    )
    (net (code "72") (name "unconnected-(IC1-PTA26-PadJ11)") (class "Default")
      (node (ref "IC1") (pin "J11") (pinfunction "PTA26_J11") (pintype "passive"))
    )
    (net (code "73") (name "unconnected-(IC1-PTA27-PadJ10)") (class "Default")
      (node (ref "IC1") (pin "J10") (pinfunction "PTA27_J10") (pintype "passive"))
    )
    (net (code "74") (name "unconnected-(IC1-PTA28-PadH12)") (class "Default")
      (node (ref "IC1") (pin "H12") (pinfunction "PTA28_H12") (pintype "passive"))
    )
    (net (code "75") (name "unconnected-(IC1-PTA29-PadH11)") (class "Default")
      (node (ref "IC1") (pin "H11") (pinfunction "PTA29_H11") (pintype "passive"))
    )
    (net (code "76") (name "unconnected-(IC1-PTB0{slash}_LLWU_P5-PadH10)") (class "Default")
      (node (ref "IC1") (pin "H10") (pinfunction "PTB0/_LLWU_P5_H10") (pintype "passive"))
    )
    (net (code "77") (name "unconnected-(IC1-PTB1-PadH9)") (class "Default")
      (node (ref "IC1") (pin "H9") (pinfunction "PTB1_H9") (pintype "passive"))
    )
    (net (code "78") (name "unconnected-(IC1-PTB2-PadG12)") (class "Default")
      (node (ref "IC1") (pin "G12") (pinfunction "PTB2_G12") (pintype "passive"))
    )
    (net (code "79") (name "unconnected-(IC1-PTB3-PadG11)") (class "Default")
      (node (ref "IC1") (pin "G11") (pinfunction "PTB3_G11") (pintype "passive"))
    )
    (net (code "80") (name "unconnected-(IC1-PTB4-PadG10)") (class "Default")
      (node (ref "IC1") (pin "G10") (pinfunction "PTB4_G10") (pintype "passive"))
    )
    (net (code "81") (name "unconnected-(IC1-PTB5-PadG9)") (class "Default")
      (node (ref "IC1") (pin "G9") (pinfunction "PTB5_G9") (pintype "passive"))
    )
    (net (code "82") (name "unconnected-(IC1-PTB6-PadF12)") (class "Default")
      (node (ref "IC1") (pin "F12") (pinfunction "PTB6_F12") (pintype "passive"))
    )
    (net (code "83") (name "unconnected-(IC1-PTB7-PadF11)") (class "Default")
      (node (ref "IC1") (pin "F11") (pinfunction "PTB7_F11") (pintype "passive"))
    )
    (net (code "84") (name "unconnected-(IC1-PTB8-PadF10)") (class "Default")
      (node (ref "IC1") (pin "F10") (pinfunction "PTB8_F10") (pintype "passive"))
    )
    (net (code "85") (name "unconnected-(IC1-PTB9-PadF9)") (class "Default")
      (node (ref "IC1") (pin "F9") (pinfunction "PTB9_F9") (pintype "passive"))
    )
    (net (code "86") (name "unconnected-(IC1-PTB18-PadD12)") (class "Default")
      (node (ref "IC1") (pin "D12") (pinfunction "PTB18_D12") (pintype "passive"))
    )
    (net (code "87") (name "unconnected-(IC1-PTB19-PadD11)") (class "Default")
      (node (ref "IC1") (pin "D11") (pinfunction "PTB19_D11") (pintype "passive"))
    )
    (net (code "88") (name "unconnected-(IC1-PTB20-PadD10)") (class "Default")
      (node (ref "IC1") (pin "D10") (pinfunction "PTB20_D10") (pintype "passive"))
    )
    (net (code "89") (name "unconnected-(IC1-PTB21-PadD9)") (class "Default")
      (node (ref "IC1") (pin "D9") (pinfunction "PTB21_D9") (pintype "passive"))
    )
    (net (code "90") (name "unconnected-(IC1-PTB22-PadC12)") (class "Default")
      (node (ref "IC1") (pin "C12") (pinfunction "PTB22_C12") (pintype "passive"))
    )
    (net (code "91") (name "unconnected-(IC1-PTB23-PadC11)") (class "Default")
      (node (ref "IC1") (pin "C11") (pinfunction "PTB23_C11") (pintype "passive"))
    )
    (net (code "92") (name "unconnected-(IC1-PTC1{slash}_LLWU_P6-PadB11)") (class "Default")
      (node (ref "IC1") (pin "B11") (pinfunction "PTC1/_LLWU_P6_B11") (pintype "passive"))
    )
    (net (code "93") (name "unconnected-(IC1-PTC2-PadA12)") (class "Default")
      (node (ref "IC1") (pin "A12") (pinfunction "PTC2_A12") (pintype "passive"))
    )
    (net (code "94") (name "unconnected-(IC1-PTC8-PadA8)") (class "Default")
      (node (ref "IC1") (pin "A8") (pinfunction "PTC8_A8") (pintype "passive"))
    )
    (net (code "95") (name "unconnected-(IC1-PTC9-PadD7)") (class "Default")
      (node (ref "IC1") (pin "D7") (pinfunction "PTC9_D7") (pintype "passive"))
    )
    (net (code "96") (name "unconnected-(IC1-PTC10-PadC7)") (class "Default")
      (node (ref "IC1") (pin "C7") (pinfunction "PTC10_C7") (pintype "passive"))
    )
    (net (code "97") (name "unconnected-(IC1-PTC11{slash}_LLWU_P11-PadB7)") (class "Default")
      (node (ref "IC1") (pin "B7") (pinfunction "PTC11/_LLWU_P11_B7") (pintype "passive"))
    )
    (net (code "98") (name "unconnected-(IC1-PTC12-PadA7)") (class "Default")
      (node (ref "IC1") (pin "A7") (pinfunction "PTC12_A7") (pintype "passive"))
    )
    (net (code "99") (name "unconnected-(IC1-PTC13-PadD6)") (class "Default")
      (node (ref "IC1") (pin "D6") (pinfunction "PTC13_D6") (pintype "passive"))
    )
    (net (code "100") (name "unconnected-(IC1-PTC14-PadC6)") (class "Default")
      (node (ref "IC1") (pin "C6") (pinfunction "PTC14_C6") (pintype "passive"))
    )
    (net (code "101") (name "unconnected-(IC1-PTC15-PadB6)") (class "Default")
      (node (ref "IC1") (pin "B6") (pinfunction "PTC15_B6") (pintype "passive"))
    )
    (net (code "102") (name "unconnected-(IC1-PTC16-PadA6)") (class "Default")
      (node (ref "IC1") (pin "A6") (pinfunction "PTC16_A6") (pintype "passive"))
    )
    (net (code "103") (name "unconnected-(IC1-PTC17-PadD5)") (class "Default")
      (node (ref "IC1") (pin "D5") (pinfunction "PTC17_D5") (pintype "passive"))
    )
    (net (code "104") (name "unconnected-(IC1-PTC18-PadC5)") (class "Default")
      (node (ref "IC1") (pin "C5") (pinfunction "PTC18_C5") (pintype "passive"))
    )
    (net (code "105") (name "unconnected-(IC1-PTC19-PadB5)") (class "Default")
      (node (ref "IC1") (pin "B5") (pinfunction "PTC19_B5") (pintype "passive"))
    )
    (net (code "106") (name "unconnected-(IC1-PTD0{slash}_LLWU_P12-PadA5)") (class "Default")
      (node (ref "IC1") (pin "A5") (pinfunction "PTD0/_LLWU_P12_A5") (pintype "passive"))
    )
    (net (code "107") (name "unconnected-(IC1-PTD1-PadD4)") (class "Default")
      (node (ref "IC1") (pin "D4") (pinfunction "PTD1_D4") (pintype "passive"))
    )
    (net (code "108") (name "unconnected-(IC1-PTD4{slash}_LLWU_P14-PadA4)") (class "Default")
      (node (ref "IC1") (pin "A4") (pinfunction "PTD4/_LLWU_P14_A4") (pintype "passive"))
    )
    (net (code "109") (name "unconnected-(IC1-PTD5-PadA3)") (class "Default")
      (node (ref "IC1") (pin "A3") (pinfunction "PTD5_A3") (pintype "passive"))
    )
    (net (code "110") (name "unconnected-(IC1-PTD6{slash}_LLWU_P15-PadA2)") (class "Default")
      (node (ref "IC1") (pin "A2") (pinfunction "PTD6/_LLWU_P15_A2") (pintype "passive"))
    )
    (net (code "111") (name "unconnected-(IC1-PTD7-PadA1)") (class "Default")
      (node (ref "IC1") (pin "A1") (pinfunction "PTD7_A1") (pintype "passive"))
    )
    (net (code "112") (name "unconnected-(IC1-PTD8{slash}LLWU_P24-PadC9)") (class "Default")
      (node (ref "IC1") (pin "C9") (pinfunction "PTD8/LLWU_P24_C9") (pintype "passive"))
    )
    (net (code "113") (name "unconnected-(IC1-PTD9-PadB9)") (class "Default")
      (node (ref "IC1") (pin "B9") (pinfunction "PTD9_B9") (pintype "passive"))
    )
    (net (code "114") (name "unconnected-(IC1-PTD10-PadB3)") (class "Default")
      (node (ref "IC1") (pin "B3") (pinfunction "PTD10_B3") (pintype "passive"))
    )
    (net (code "115") (name "unconnected-(IC1-PTD11{slash}LLWU_P25-PadB2)") (class "Default")
      (node (ref "IC1") (pin "B2") (pinfunction "PTD11/LLWU_P25_B2") (pintype "passive"))
    )
    (net (code "116") (name "unconnected-(IC1-PTD12-PadB1)") (class "Default")
      (node (ref "IC1") (pin "B1") (pinfunction "PTD12_B1") (pintype "passive"))
    )
    (net (code "117") (name "unconnected-(IC1-PTD13-PadC3)") (class "Default")
      (node (ref "IC1") (pin "C3") (pinfunction "PTD13_C3") (pintype "passive"))
    )
    (net (code "118") (name "unconnected-(IC1-PTD14-PadC2)") (class "Default")
      (node (ref "IC1") (pin "C2") (pinfunction "PTD14_C2") (pintype "passive"))
    )
    (net (code "119") (name "unconnected-(IC1-PTD15-PadC1)") (class "Default")
      (node (ref "IC1") (pin "C1") (pinfunction "PTD15_C1") (pintype "passive"))
    )
    (net (code "120") (name "unconnected-(IC1-PTE0-PadD3)") (class "Default")
      (node (ref "IC1") (pin "D3") (pinfunction "PTE0_D3") (pintype "passive"))
    )
    (net (code "121") (name "unconnected-(IC1-PTE1{slash}LLWU_P0-PadD2)") (class "Default")
      (node (ref "IC1") (pin "D2") (pinfunction "PTE1/LLWU_P0_D2") (pintype "passive"))
    )
    (net (code "122") (name "unconnected-(IC1-PTE2{slash}LLWU_P1-PadD1)") (class "Default")
      (node (ref "IC1") (pin "D1") (pinfunction "PTE2/LLWU_P1_D1") (pintype "passive"))
    )
    (net (code "123") (name "unconnected-(IC1-PTE3-PadE4)") (class "Default")
      (node (ref "IC1") (pin "E4") (pinfunction "PTE3_E4") (pintype "passive"))
    )
    (net (code "124") (name "unconnected-(IC1-PTE4{slash}LLWU{slash}P2-PadE3)") (class "Default")
      (node (ref "IC1") (pin "E3") (pinfunction "PTE4/LLWU/P2_E3") (pintype "passive"))
    )
    (net (code "125") (name "unconnected-(IC1-PTE5-PadE2)") (class "Default")
      (node (ref "IC1") (pin "E2") (pinfunction "PTE5_E2") (pintype "passive"))
    )
    (net (code "126") (name "unconnected-(IC1-PTE7-PadF4)") (class "Default")
      (node (ref "IC1") (pin "F4") (pinfunction "PTE7_F4") (pintype "passive"))
    )
    (net (code "127") (name "unconnected-(IC1-PTE8-PadF3)") (class "Default")
      (node (ref "IC1") (pin "F3") (pinfunction "PTE8_F3") (pintype "passive"))
    )
    (net (code "128") (name "unconnected-(IC1-PTE9{slash}LLWU_P17-PadF2)") (class "Default")
      (node (ref "IC1") (pin "F2") (pinfunction "PTE9/LLWU_P17_F2") (pintype "passive"))
    )
    (net (code "129") (name "unconnected-(IC1-PTE10{slash}LLWU_P18-PadF1)") (class "Default")
      (node (ref "IC1") (pin "F1") (pinfunction "PTE10/LLWU_P18_F1") (pintype "passive"))
    )
    (net (code "130") (name "unconnected-(IC1-PTE11-PadG4)") (class "Default")
      (node (ref "IC1") (pin "G4") (pinfunction "PTE11_G4") (pintype "passive"))
    )
    (net (code "131") (name "unconnected-(IC1-PTE12-PadG3)") (class "Default")
      (node (ref "IC1") (pin "G3") (pinfunction "PTE12_G3") (pintype "passive"))
    )
    (net (code "132") (name "unconnected-(IC1-PTE24-PadM4)") (class "Default")
      (node (ref "IC1") (pin "M4") (pinfunction "PTE24_M4") (pintype "passive"))
    )
    (net (code "133") (name "unconnected-(IC1-PTE25{slash}LLWU_P21-PadK5)") (class "Default")
      (node (ref "IC1") (pin "K5") (pinfunction "PTE25/LLWU_P21_K5") (pintype "passive"))
    )
    (net (code "134") (name "unconnected-(IC1-PTE26-PadK4)") (class "Default")
      (node (ref "IC1") (pin "K4") (pinfunction "PTE26_K4") (pintype "passive"))
    )
    (net (code "135") (name "unconnected-(IC1-PTE27-PadJ4)") (class "Default")
      (node (ref "IC1") (pin "J4") (pinfunction "PTE27_J4") (pintype "passive"))
    )
    (net (code "136") (name "unconnected-(IC1-PTE28-PadH4)") (class "Default")
      (node (ref "IC1") (pin "H4") (pinfunction "PTE28_H4") (pintype "passive"))
    )
    (net (code "137") (name "unconnected-(IC1-RTC_WAKEUP_B-PadL5)") (class "Default")
      (node (ref "IC1") (pin "L5") (pinfunction "RTC_WAKEUP_B_L5") (pintype "passive"))
    )
    (net (code "138") (name "unconnected-(IC1-VREG_IN1-PadJ2)") (class "Default")
      (node (ref "IC1") (pin "J2") (pinfunction "VREG_IN1_J2") (pintype "passive"))
    )
    (net (code "139") (name "unconnected-(IC3-PTA0{slash}IRQ_0-Pad14)") (class "Default")
      (node (ref "IC3") (pin "14") (pinfunction "PTA0/IRQ_0_14") (pintype "passive"))
    )
    (net (code "140") (name "unconnected-(IC3-PTA1{slash}IRQ_1{slash}LPTMR0_ALT1-Pad15)") (class "Default")
      (node (ref "IC3") (pin "15") (pinfunction "PTA1/IRQ_1/LPTMR0_ALT1_15") (pintype "passive"))
    )
    (net (code "141") (name "unconnected-(IC3-PTA2-Pad16)") (class "Default")
      (node (ref "IC3") (pin "16") (pinfunction "PTA2_16") (pintype "passive"))
    )
    (net (code "142") (name "unconnected-(IC3-PTA5-Pad5)") (class "Default")
      (node (ref "IC3") (pin "5") (pinfunction "PTA5_5") (pintype "passive"))
    )
    (net (code "143") (name "unconnected-(IC3-PTB3{slash}IRQ_10-Pad11)") (class "Default")
      (node (ref "IC3") (pin "11") (pinfunction "PTB3/IRQ_10_11") (pintype "passive"))
    )
    (net (code "144") (name "unconnected-(IC3-PTB4{slash}IRQ_11-Pad12)") (class "Default")
      (node (ref "IC3") (pin "12") (pinfunction "PTB4/IRQ_11_12") (pintype "passive"))
    )
    (net (code "145") (name "unconnected-(J1-ID-Pad4)") (class "Default")
      (node (ref "J1") (pin "4") (pinfunction "ID_4") (pintype "bidirectional"))
    )
    (net (code "146") (name "unconnected-(PS1-N{slash}C-Pad3)") (class "Default")
      (node (ref "PS1") (pin "3") (pinfunction "N/C_3") (pintype "passive"))
    )
    (net (code "147") (name "unconnected-(S1-Pad1)") (class "Default")
      (node (ref "S1") (pin "1") (pinfunction "1_1") (pintype "passive"))
    )
    (net (code "148") (name "unconnected-(S1-Pad4)") (class "Default")
      (node (ref "S1") (pin "4") (pinfunction "4_4") (pintype "passive"))
    )
  )
)
